# CAN_Devices.net
KiCad netlist of a schematic drawn in Altium Designer
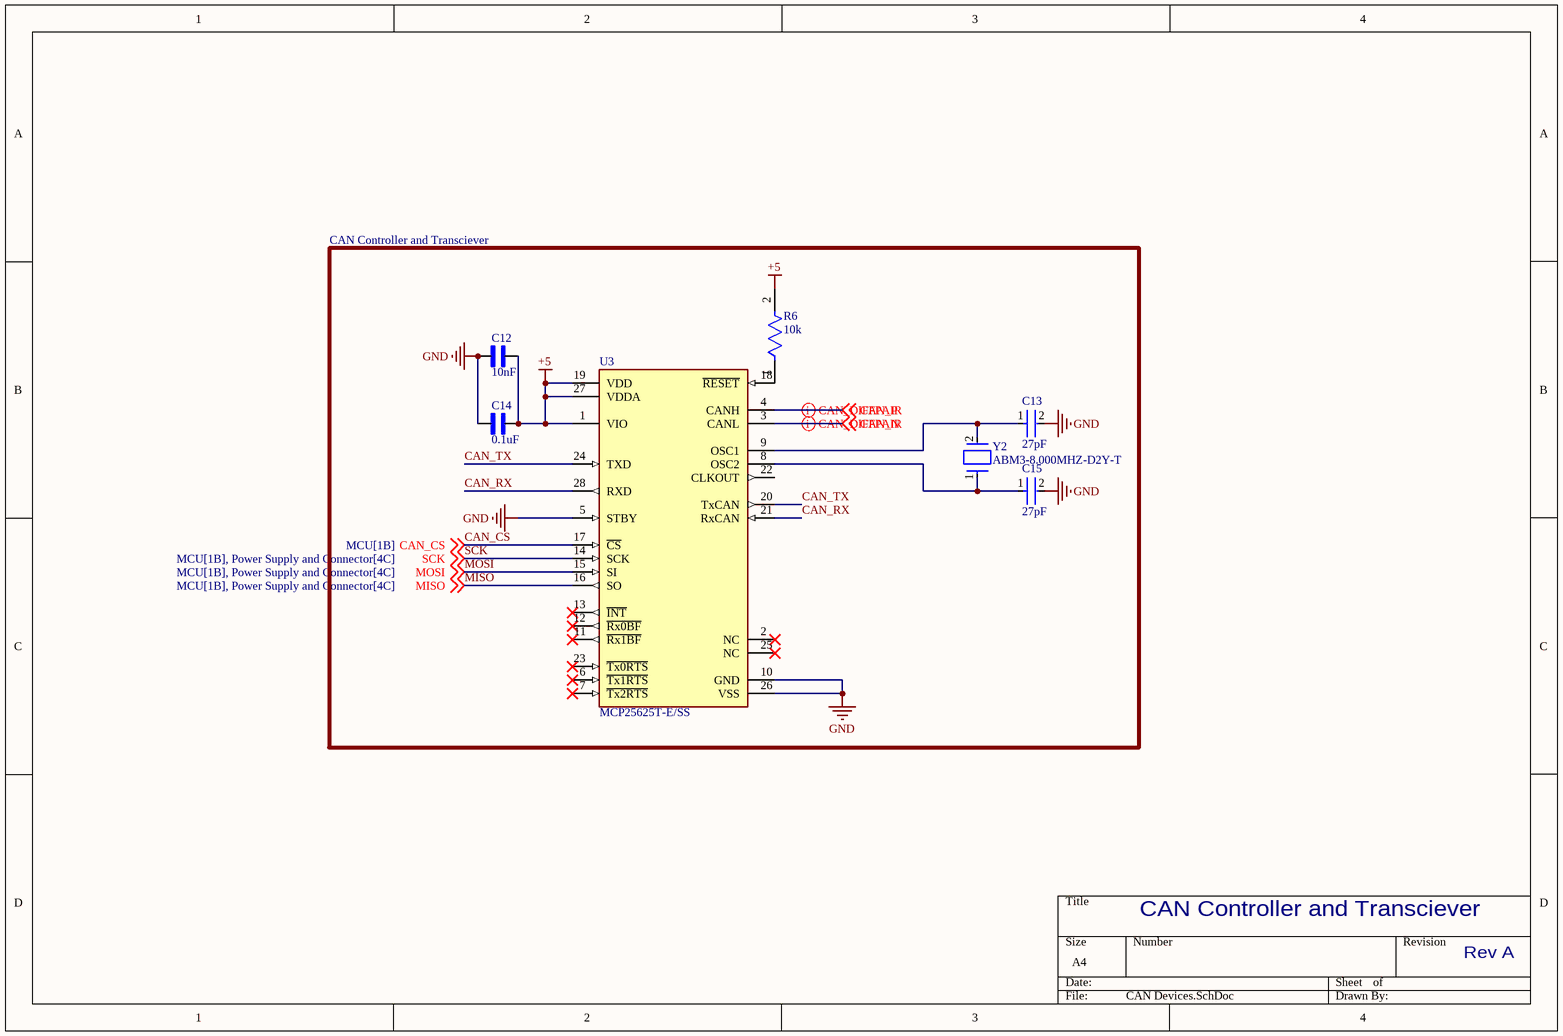
[diagram p0: CAN Devices.SchDoc]

(export (version "E")
  (design (tool "Eeschema 10.0.6"))
  (components
    (comp (ref "C12")
      (value "10nF")
      (footprint "C0805C103F5GACTU:CAPC2012X88N")
      (description "CAP CER 10000PF 50V C0G/NP0 0805")
      (fields (field (name "MF") "{'manufacturer': u'KEMET'}") (field (name "MP") "C0805C103F5GACTU"))
      (libsource (lib "*") (part "C0805C103F5GACTU"))
    )
    (comp (ref "C13")
      (value "27pF")
      (footprint "FP-0805-L_2_01_0_2-W_1_25-MFG")
      (description "General Purpose Ceramic Capacitor, 0805, 27pF, 5%, C0G, 30ppm/°C, 50V")
      (fields (field (name "VOLTAGE") "50V") (field (name "TOLERANCE") "5%"))
      (libsource (lib "Altium Content Vault") (part "02cd4be3c70576c341d710602a673aa"))
    )
    (comp (ref "C14")
      (value "0.1uF")
      (footprint "GCM21BR71H104KA37L:CAPC2012X135N")
      (description "CAP, MLCC, X7R, 0.1UF, 50V, 0805")
      (fields (field (name "MF") "{'manufacturer': u'Murata'}") (field (name "MP") "GCM21BR71H104KA37L"))
      (libsource (lib "*") (part "GCM21BR71H104KA37L"))
    )
    (comp (ref "C15")
      (value "27pF")
      (footprint "FP-0805-L_2_01_0_2-W_1_25-MFG")
      (description "General Purpose Ceramic Capacitor, 0805, 27pF, 5%, C0G, 30ppm/°C, 50V")
      (fields (field (name "VOLTAGE") "50V") (field (name "TOLERANCE") "5%"))
      (libsource (lib "Altium Content Vault") (part "02cd4be3c70576c341d710602a673aa"))
    )
    (comp (ref "R6")
      (value "10k")
      (footprint "FP-CRCW0805-e3-IPC_A")
      (description "RES Thick Film, 10kΩ, 1%, 0.125W, 100ppm/°C, 0805")
      (fields (field (name "TOLERANCE") "1%"))
      (libsource (lib "Altium Content Vault") (part "1029c3af85768c4190bb7ad29bc67b5"))
    )
    (comp (ref "U3")
      (value "MCP25625T-E/SS")
      (footprint "FP-C04-073-IPC_B")
      (description "IC TRANSCEIVER 1/1 28SSOP")
      (libsource (lib "Altium Content Vault") (part "1eb43db0d86e80dbea2ef2edec005e1"))
    )
    (comp (ref "Y2")
      (value "ABM3-8.000MHZ-D2Y-T")
      (footprint "FP-ABM3-MFG")
      (description "Crystal 8MHz ±20ppm 18pF SMD-2 5mm x 3.2mm")
      (fields (field (name "TOLERANCE") "20ppm"))
      (libsource (lib "Altium Content Vault") (part "c23a69dc6c9e2f18f2079038eb95dd1"))
    )
  )
  (nets
    (net (code "1") (name "+5") (class "Default")
      (node (ref "C12") (pin "1") (pinfunction "1_1") (pintype "passive"))
      (node (ref "C14") (pin "1") (pinfunction "1_1") (pintype "passive"))
      (node (ref "R6") (pin "2") (pinfunction "2_2") (pintype "passive"))
      (node (ref "U3") (pin "1") (pinfunction "VIO_1") (pintype "power_in"))
      (node (ref "U3") (pin "19") (pinfunction "VDD_19") (pintype "power_in"))
      (node (ref "U3") (pin "27") (pinfunction "VDDA_27") (pintype "power_in"))
    )
    (net (code "2") (name "/CAN_RX") (class "Default")
      (node (ref "U3") (pin "21") (pinfunction "RxCAN_21") (pintype "input"))
      (node (ref "U3") (pin "28") (pinfunction "RXD_28") (pintype "output"))
    )
    (net (code "3") (name "/CAN_TX") (class "Default")
      (node (ref "U3") (pin "20") (pinfunction "TxCAN_20") (pintype "output"))
      (node (ref "U3") (pin "24") (pinfunction "TXD_24") (pintype "input"))
    )
    (net (code "4") (name "CAN_CS") (class "Default")
      (node (ref "U3") (pin "17") (pinfunction "~{CS}_17") (pintype "input"))
    )
    (net (code "5") (name "CAN_N") (class "Default")
      (node (ref "U3") (pin "3") (pinfunction "CANL_3") (pintype "passive"))
    )
    (net (code "6") (name "CAN_P") (class "Default")
      (node (ref "U3") (pin "4") (pinfunction "CANH_4") (pintype "passive"))
    )
    (net (code "7") (name "GND") (class "Default")
      (node (ref "C12") (pin "2") (pinfunction "2_2") (pintype "passive"))
      (node (ref "C13") (pin "2") (pinfunction "2_2") (pintype "passive"))
      (node (ref "C14") (pin "2") (pinfunction "2_2") (pintype "passive"))
      (node (ref "C15") (pin "2") (pinfunction "2_2") (pintype "passive"))
      (node (ref "U3") (pin "10") (pinfunction "GND_10") (pintype "power_in"))
      (node (ref "U3") (pin "26") (pinfunction "VSS_26") (pintype "power_in"))
      (node (ref "U3") (pin "5") (pinfunction "STBY_5") (pintype "input"))
    )
    (net (code "8") (name "MISO") (class "Default")
      (node (ref "U3") (pin "16") (pinfunction "SO_16") (pintype "output"))
    )
    (net (code "9") (name "MOSI") (class "Default")
      (node (ref "U3") (pin "15") (pinfunction "SI_15") (pintype "input"))
    )
    (net (code "10") (name "Net-(U3-OSC1)") (class "Default")
      (node (ref "C13") (pin "1") (pinfunction "1_1") (pintype "passive"))
      (node (ref "U3") (pin "9") (pinfunction "OSC1_9") (pintype "passive"))
      (node (ref "Y2") (pin "2") (pinfunction "2_2") (pintype "passive"))
    )
    (net (code "11") (name "Net-(U3-OSC2)") (class "Default")
      (node (ref "C15") (pin "1") (pinfunction "1_1") (pintype "passive"))
      (node (ref "U3") (pin "8") (pinfunction "OSC2_8") (pintype "passive"))
      (node (ref "Y2") (pin "1") (pinfunction "1_1") (pintype "passive"))
    )
    (net (code "12") (name "Net-(U3-~{RESET})") (class "Default")
      (node (ref "R6") (pin "1") (pinfunction "1_1") (pintype "power_in"))
      (node (ref "U3") (pin "18") (pinfunction "~{RESET}_18") (pintype "input"))
    )
    (net (code "13") (name "SCK") (class "Default")
      (node (ref "U3") (pin "14") (pinfunction "SCK_14") (pintype "input"))
    )
    (net (code "14") (name "unconnected-(U3-CLKOUT-Pad22)") (class "Default")
      (node (ref "U3") (pin "22") (pinfunction "CLKOUT_22") (pintype "output"))
    )
    (net (code "15") (name "unconnected-(U3-NC-Pad2)") (class "Default")
      (node (ref "U3") (pin "2") (pinfunction "NC_2") (pintype "passive+no_connect"))
    )
    (net (code "16") (name "unconnected-(U3-NC-Pad25)") (class "Default")
      (node (ref "U3") (pin "25") (pinfunction "NC_25") (pintype "passive+no_connect"))
    )
    (net (code "17") (name "unconnected-(U3-~{INT}-Pad13)") (class "Default")
      (node (ref "U3") (pin "13") (pinfunction "~{INT}_13") (pintype "output+no_connect"))
    )
    (net (code "18") (name "unconnected-(U3-~{Rx0BF}-Pad12)") (class "Default")
      (node (ref "U3") (pin "12") (pinfunction "~{Rx0BF}_12") (pintype "output+no_connect"))
    )
    (net (code "19") (name "unconnected-(U3-~{Rx1BF}-Pad11)") (class "Default")
      (node (ref "U3") (pin "11") (pinfunction "~{Rx1BF}_11") (pintype "output+no_connect"))
    )
    (net (code "20") (name "unconnected-(U3-~{Tx0RTS}-Pad23)") (class "Default")
      (node (ref "U3") (pin "23") (pinfunction "~{Tx0RTS}_23") (pintype "input+no_connect"))
    )
    (net (code "21") (name "unconnected-(U3-~{Tx1RTS}-Pad6)") (class "Default")
      (node (ref "U3") (pin "6") (pinfunction "~{Tx1RTS}_6") (pintype "input+no_connect"))
    )
    (net (code "22") (name "unconnected-(U3-~{Tx2RTS}-Pad7)") (class "Default")
      (node (ref "U3") (pin "7") (pinfunction "~{Tx2RTS}_7") (pintype "input+no_connect"))
    )
  )
)
